# 2023-04-10.net
KiCad netlist of a schematic drawn in Altium Designer
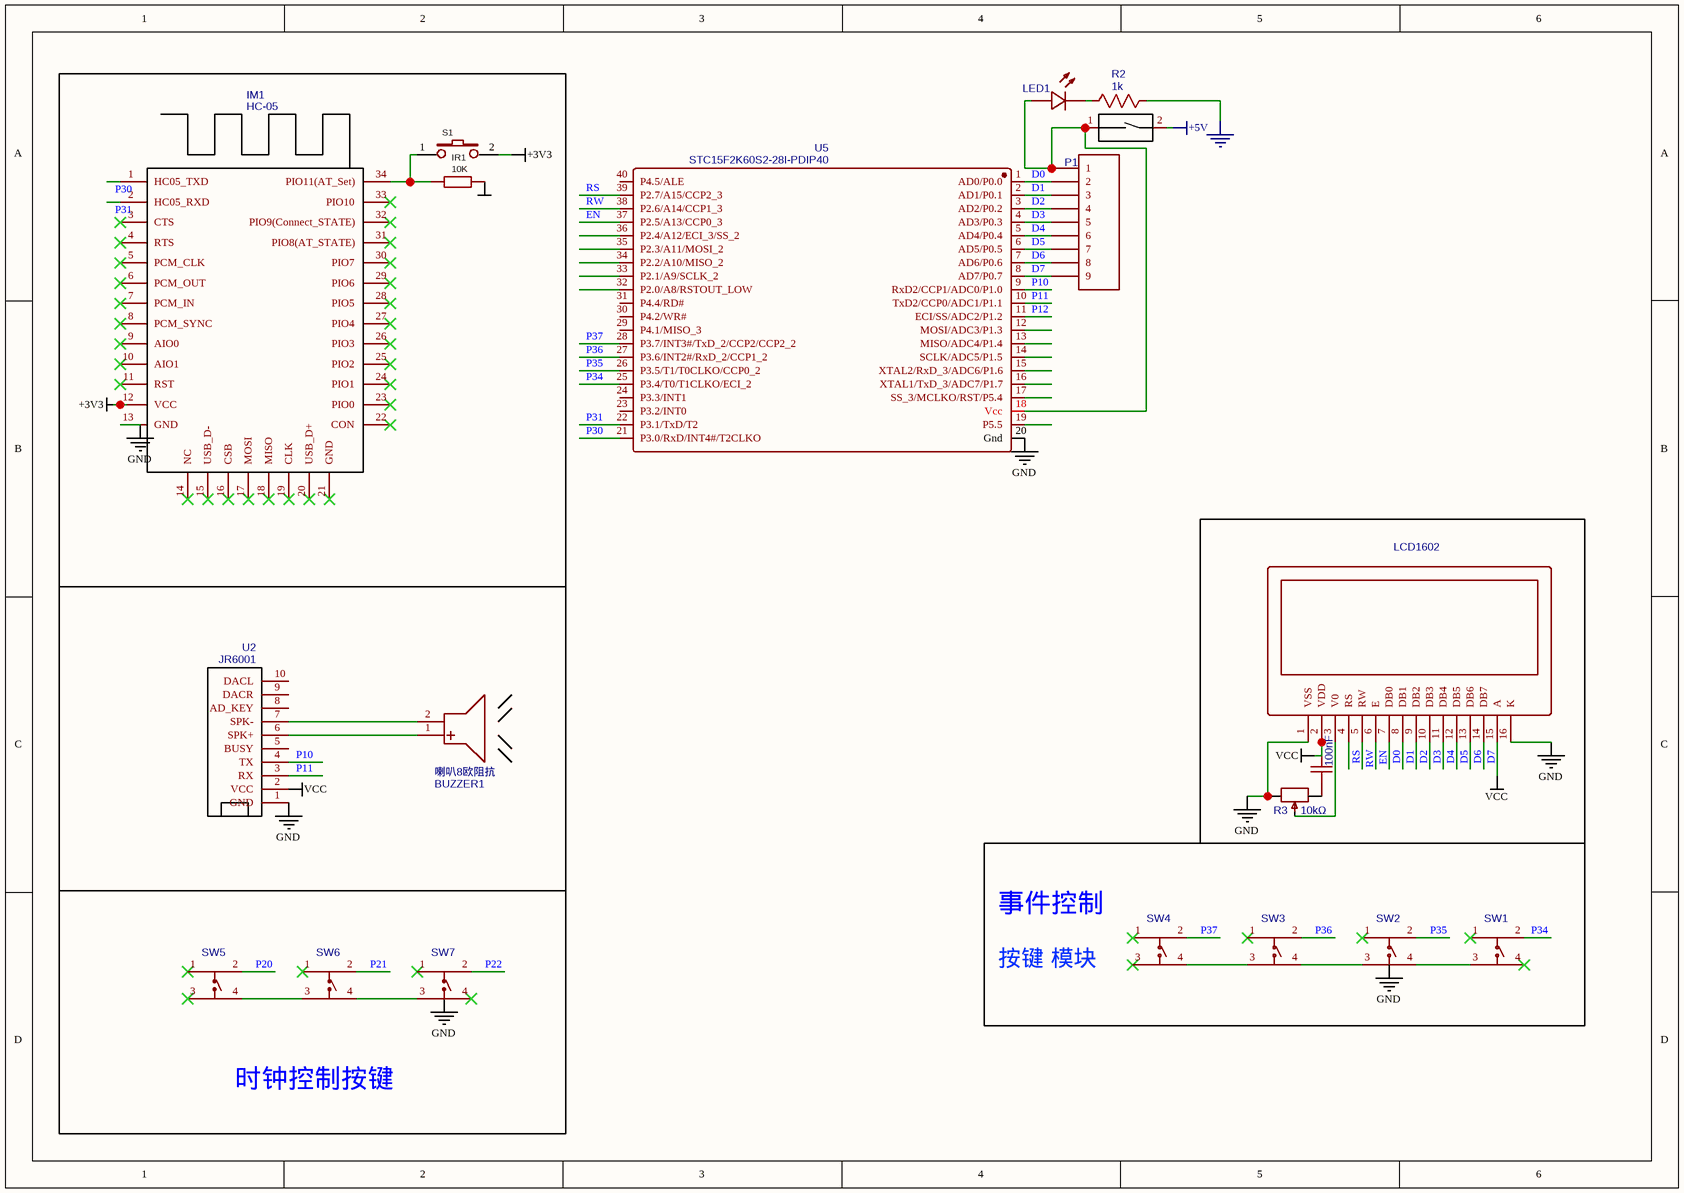
[diagram p0: 多功能遥控门铃的设计_2023-04-10.schdoc]

(export (version "E")
  (design (tool "Eeschema 10.0.6"))
  (components
    (comp (ref "BUZZER1")
      (value "喇叭8欧阻抗")
      (fields
        (field (name "BOM_SUPPLIER PART") "C265130")
        (field (name "BOM_MANUFACTURER PART") "GMD0955YB-12V2700")
        (field (name "CONTRIBUTOR") "kennen")
      )
      (libsource (lib "altium-import") (part "root_0_喇叭8欧阻抗_"))
    )
    (comp (ref "C1")
      (value "100nF")
      (fields
        (field (name "BOM_SUPPLIER PART") "C327271")
        (field (name "BOM_MANUFACTURER PART") "CC0402MRY5V8BB104")
        (field (name "CONTRIBUTOR") "LCSC")
      )
      (libsource (lib "altium-import") (part "root_1_100nF_"))
    )
    (comp (ref "DIP1")
      (value "VDG/S-01L blue")
      (fields (field (name "BOM_SUPPLIER PART") "C47086"))
      (libsource (lib "altium-import") (part "root_0_VDG/S-01L blue_"))
    )
    (comp (ref "IKEY1")
      (value "S1")
      (fields
        (field (name "BOM_MANUFACTURER PART") "直插轻触开关 6*6*9.5")
        (field (name "CONTRIBUTOR") "Zhang9999999")
      )
      (libsource (lib "altium-import") (part "root_0_S1_"))
    )
    (comp (ref "IM1")
      (value "HC-05")
      (fields (field (name "CONTRIBUTOR") "luohaiyang"))
      (libsource (lib "altium-import") (part "root_0_HC-05_"))
    )
    (comp (ref "IR1")
      (value "10K")
      (fields (field (name "BOM_MANUFACTURER PART") "?"))
      (libsource (lib "altium-import") (part "root_0_10K_"))
    )
    (comp (ref "LCD1602")
      (value "1")
      (fields
        (field (name "BOM_MANUFACTURER PART") "LCM1602K-NSW-BBW-33V33")
        (field (name "BOM_SUPPLIER PART") "C83272")
      )
      (libsource (lib "altium-import") (part "root_0_1_"))
    )
    (comp (ref "LED1")
      (value "LED-3MM")
      (fields
        (field (name "BOM_SUPPLIER PART") "C99772")
        (field (name "BOM_MANUFACTURER PART") "204-10SURD/S530-A3")
      )
      (libsource (lib "altium-import") (part "root_0_LED-3MM_"))
    )
    (comp (ref "P1")
      (value "SIP9")
      (fields (field (name "BOM_MANUFACTURER PART") "?"))
      (libsource (lib "altium-import") (part "root_0_SIP9_"))
    )
    (comp (ref "R2")
      (value "1k")
      (fields (field (name "BOM_MANUFACTURER PART") "?"))
      (libsource (lib "altium-import") (part "root_2_1k_"))
    )
    (comp (ref "R3")
      (value "10kΩ")
      (fields
        (field (name "BOM_MANUFACTURER PART") "3296W-1-103LF")
        (field (name "BOM_SUPPLIER PART") "C34846")
      )
      (libsource (lib "altium-import") (part "root_1_10kΩ_"))
    )
    (comp (ref "SW1")
      (value "KH-6X6X6H-STM")
      (fields (field (name "BOM_SUPPLIER PART") "C2837532") (field (name "CONTRIBUTOR") "LCSC"))
      (libsource (lib "altium-import") (part "root_0_KH-6X6X6H-STM_"))
    )
    (comp (ref "SW2")
      (value "KH-6X6X6H-STM")
      (fields (field (name "BOM_SUPPLIER PART") "C2837532") (field (name "CONTRIBUTOR") "LCSC"))
      (libsource (lib "altium-import") (part "root_0_KH-6X6X6H-STM_"))
    )
    (comp (ref "SW3")
      (value "KH-6X6X6H-STM")
      (fields (field (name "BOM_SUPPLIER PART") "C2837532") (field (name "CONTRIBUTOR") "LCSC"))
      (libsource (lib "altium-import") (part "root_0_KH-6X6X6H-STM_"))
    )
    (comp (ref "SW4")
      (value "KH-6X6X6H-STM")
      (fields (field (name "BOM_SUPPLIER PART") "C2837532") (field (name "CONTRIBUTOR") "LCSC"))
      (libsource (lib "altium-import") (part "root_0_KH-6X6X6H-STM_"))
    )
    (comp (ref "SW5")
      (value "KH-6X6X6H-STM")
      (fields (field (name "BOM_SUPPLIER PART") "C2837532") (field (name "CONTRIBUTOR") "LCSC"))
      (libsource (lib "altium-import") (part "root_0_KH-6X6X6H-STM_"))
    )
    (comp (ref "SW6")
      (value "KH-6X6X6H-STM")
      (fields (field (name "BOM_SUPPLIER PART") "C2837532") (field (name "CONTRIBUTOR") "LCSC"))
      (libsource (lib "altium-import") (part "root_0_KH-6X6X6H-STM_"))
    )
    (comp (ref "SW7")
      (value "KH-6X6X6H-STM")
      (fields (field (name "BOM_SUPPLIER PART") "C2837532") (field (name "CONTRIBUTOR") "LCSC"))
      (libsource (lib "altium-import") (part "root_0_KH-6X6X6H-STM_"))
    )
    (comp (ref "U2")
      (value "JR6001")
      (fields (field (name "CONTRIBUTOR") "212308jiangyuhao"))
      (libsource (lib "altium-import") (part "root_0_JR6001_"))
    )
    (comp (ref "U5")
      (value "STC15F2K60S2-28I-PDIP40")
      (fields (field (name "BOM_SUPPLIER PART") "C57308"))
      (libsource (lib "altium-import") (part "root_0_STC15F2K60S2-28I-PDIP40_"))
    )
  )
  (nets
    (net (code "1") (name "+3V3") (class "Default")
      (node (ref "IKEY1") (pin "2") (pinfunction "3_2") (pintype "passive"))
      (node (ref "IM1") (pin "12") (pinfunction "VCC_12") (pintype "passive"))
    )
    (net (code "2") (name "+5V") (class "Default")
      (node (ref "DIP1") (pin "2") (pinfunction "2_2") (pintype "passive"))
    )
    (net (code "3") (name "/D0") (class "Default")
      (node (ref "LCD1602") (pin "7") (pinfunction "DB0_7") (pintype "passive"))
      (node (ref "P1") (pin "2") (pinfunction "2_2") (pintype "passive"))
      (node (ref "U5") (pin "1") (pinfunction "AD0/P0.0_1") (pintype "passive"))
    )
    (net (code "4") (name "/D1") (class "Default")
      (node (ref "LCD1602") (pin "8") (pinfunction "DB1_8") (pintype "passive"))
      (node (ref "P1") (pin "3") (pinfunction "3_3") (pintype "passive"))
      (node (ref "U5") (pin "2") (pinfunction "AD1/P0.1_2") (pintype "passive"))
    )
    (net (code "5") (name "/D2") (class "Default")
      (node (ref "LCD1602") (pin "9") (pinfunction "DB2_9") (pintype "passive"))
      (node (ref "P1") (pin "4") (pinfunction "4_4") (pintype "passive"))
      (node (ref "U5") (pin "3") (pinfunction "AD2/P0.2_3") (pintype "passive"))
    )
    (net (code "6") (name "/D3") (class "Default")
      (node (ref "LCD1602") (pin "10") (pinfunction "DB3_10") (pintype "passive"))
      (node (ref "P1") (pin "5") (pinfunction "5_5") (pintype "passive"))
      (node (ref "U5") (pin "4") (pinfunction "AD3/P0.3_4") (pintype "passive"))
    )
    (net (code "7") (name "/D4") (class "Default")
      (node (ref "LCD1602") (pin "11") (pinfunction "DB4_11") (pintype "passive"))
      (node (ref "P1") (pin "6") (pinfunction "6_6") (pintype "passive"))
      (node (ref "U5") (pin "5") (pinfunction "AD4/P0.4_5") (pintype "passive"))
    )
    (net (code "8") (name "/D5") (class "Default")
      (node (ref "LCD1602") (pin "12") (pinfunction "DB5_12") (pintype "passive"))
      (node (ref "P1") (pin "7") (pinfunction "7_7") (pintype "passive"))
      (node (ref "U5") (pin "6") (pinfunction "AD5/P0.5_6") (pintype "passive"))
    )
    (net (code "9") (name "/D6") (class "Default")
      (node (ref "LCD1602") (pin "13") (pinfunction "DB6_13") (pintype "passive"))
      (node (ref "P1") (pin "8") (pinfunction "8_8") (pintype "passive"))
      (node (ref "U5") (pin "7") (pinfunction "AD6/P0.6_7") (pintype "passive"))
    )
    (net (code "10") (name "/D7") (class "Default")
      (node (ref "LCD1602") (pin "14") (pinfunction "DB7_14") (pintype "passive"))
      (node (ref "P1") (pin "9") (pinfunction "9_9") (pintype "passive"))
      (node (ref "U5") (pin "8") (pinfunction "AD7/P0.7_8") (pintype "passive"))
    )
    (net (code "11") (name "/EN") (class "Default")
      (node (ref "LCD1602") (pin "6") (pinfunction "E_6") (pintype "passive"))
      (node (ref "U5") (pin "37") (pinfunction "P2.5/A13/CCP0_3_37") (pintype "passive"))
    )
    (net (code "12") (name "/P10") (class "Default")
      (node (ref "U2") (pin "4") (pinfunction "TX_4") (pintype "passive"))
      (node (ref "U5") (pin "9") (pinfunction "RxD2/CCP1/ADC0/P1.0_9") (pintype "passive"))
    )
    (net (code "13") (name "/P11") (class "Default")
      (node (ref "U2") (pin "3") (pinfunction "RX_3") (pintype "passive"))
      (node (ref "U5") (pin "10") (pinfunction "TxD2/CCP0/ADC1/P1.1_10") (pintype "passive"))
    )
    (net (code "14") (name "/P12") (class "Default")
      (node (ref "U5") (pin "11") (pinfunction "ECI/SS/ADC2/P1.2_11") (pintype "passive"))
    )
    (net (code "15") (name "/P20") (class "Default")
      (node (ref "SW5") (pin "2") (pinfunction "B_2") (pintype "passive"))
    )
    (net (code "16") (name "/P21") (class "Default")
      (node (ref "SW6") (pin "2") (pinfunction "B_2") (pintype "passive"))
    )
    (net (code "17") (name "/P22") (class "Default")
      (node (ref "SW7") (pin "2") (pinfunction "B_2") (pintype "passive"))
    )
    (net (code "18") (name "/P30") (class "Default")
      (node (ref "U5") (pin "21") (pinfunction "P3.0/RxD/INT4#/T2CLKO_21") (pintype "passive"))
    )
    (net (code "19") (name "/P31") (class "Default")
      (node (ref "U5") (pin "22") (pinfunction "P3.1/TxD/T2_22") (pintype "passive"))
    )
    (net (code "20") (name "/P34") (class "Default")
      (node (ref "SW1") (pin "2") (pinfunction "B_2") (pintype "passive"))
      (node (ref "U5") (pin "25") (pinfunction "P3.4/T0/T1CLKO/ECI_2_25") (pintype "passive"))
    )
    (net (code "21") (name "/P35") (class "Default")
      (node (ref "SW2") (pin "2") (pinfunction "B_2") (pintype "passive"))
      (node (ref "U5") (pin "26") (pinfunction "P3.5/T1/T0CLKO/CCP0_2_26") (pintype "passive"))
    )
    (net (code "22") (name "/P36") (class "Default")
      (node (ref "SW3") (pin "2") (pinfunction "B_2") (pintype "passive"))
      (node (ref "U5") (pin "27") (pinfunction "P3.6/INT2#/RxD_2/CCP1_2_27") (pintype "passive"))
    )
    (net (code "23") (name "/P37") (class "Default")
      (node (ref "SW4") (pin "2") (pinfunction "B_2") (pintype "passive"))
      (node (ref "U5") (pin "28") (pinfunction "P3.7/INT3#/TxD_2/CCP2/CCP2_2_28") (pintype "passive"))
    )
    (net (code "24") (name "/RS") (class "Default")
      (node (ref "LCD1602") (pin "4") (pinfunction "RS_4") (pintype "passive"))
      (node (ref "U5") (pin "39") (pinfunction "P2.7/A15/CCP2_3_39") (pintype "passive"))
    )
    (net (code "25") (name "/RW") (class "Default")
      (node (ref "LCD1602") (pin "5") (pinfunction "RW_5") (pintype "passive"))
      (node (ref "U5") (pin "38") (pinfunction "P2.6/A14/CCP1_3_38") (pintype "passive"))
    )
    (net (code "26") (name "GND") (class "Default")
      (node (ref "IM1") (pin "13") (pinfunction "GND_13") (pintype "passive"))
      (node (ref "IR1") (pin "2") (pinfunction "2_2") (pintype "passive"))
      (node (ref "LCD1602") (pin "1") (pinfunction "VSS_1") (pintype "passive"))
      (node (ref "LCD1602") (pin "16") (pinfunction "K_16") (pintype "passive"))
      (node (ref "R2") (pin "1") (pinfunction "1_1") (pintype "passive"))
      (node (ref "R3") (pin "1") (pinfunction "1_1") (pintype "passive"))
      (node (ref "U2") (pin "1") (pinfunction "GND_1") (pintype "passive"))
      (node (ref "U5") (pin "20") (pinfunction "Gnd_20") (pintype "passive"))
    )
    (net (code "27") (name "Net-(BUZZER1-+)") (class "Default")
      (node (ref "BUZZER1") (pin "1") (pinfunction "+_1") (pintype "passive"))
      (node (ref "U2") (pin "6") (pinfunction "SPK+_6") (pintype "passive"))
    )
    (net (code "28") (name "Net-(BUZZER1--)") (class "Default")
      (node (ref "BUZZER1") (pin "2") (pinfunction "-_2") (pintype "passive"))
      (node (ref "U2") (pin "7") (pinfunction "SPK-_7") (pintype "passive"))
    )
    (net (code "29") (name "Net-(C1-Pad1)") (class "Default")
      (node (ref "C1") (pin "1") (pinfunction "1_1") (pintype "passive"))
      (node (ref "R3") (pin "3") (pinfunction "3_3") (pintype "passive"))
    )
    (net (code "30") (name "Net-(IM1-PIO11(AT_Set))") (class "Default")
      (node (ref "IKEY1") (pin "1") (pinfunction "1_1") (pintype "passive"))
      (node (ref "IM1") (pin "34") (pinfunction "PIO11(AT_Set)_34") (pintype "passive"))
      (node (ref "IR1") (pin "1") (pinfunction "1_1") (pintype "passive"))
    )
    (net (code "31") (name "Net-(LCD1602-V0)") (class "Default")
      (node (ref "LCD1602") (pin "3") (pinfunction "V0_3") (pintype "passive"))
      (node (ref "R3") (pin "2") (pinfunction "2_2") (pintype "passive"))
    )
    (net (code "32") (name "Net-(LED1-+)") (class "Default")
      (node (ref "DIP1") (pin "1") (pinfunction "1_1") (pintype "passive"))
      (node (ref "LED1") (pin "1") (pinfunction "+_1") (pintype "passive"))
      (node (ref "P1") (pin "1") (pinfunction "1_1") (pintype "passive"))
      (node (ref "U5") (pin "18") (pinfunction "Vcc_18") (pintype "passive"))
    )
    (net (code "33") (name "Net-(LED1--)") (class "Default")
      (node (ref "LED1") (pin "2") (pinfunction "-_2") (pintype "passive"))
      (node (ref "R2") (pin "2") (pinfunction "2_2") (pintype "passive"))
    )
    (net (code "34") (name "Net-(SW1-C)") (class "Default")
      (node (ref "SW1") (pin "3") (pinfunction "C_3") (pintype "passive"))
      (node (ref "SW2") (pin "4") (pinfunction "D_4") (pintype "passive"))
    )
    (net (code "35") (name "Net-(SW2-C)") (class "Default")
      (node (ref "SW2") (pin "3") (pinfunction "C_3") (pintype "passive"))
      (node (ref "SW3") (pin "4") (pinfunction "D_4") (pintype "passive"))
    )
    (net (code "36") (name "Net-(SW3-C)") (class "Default")
      (node (ref "SW3") (pin "3") (pinfunction "C_3") (pintype "passive"))
      (node (ref "SW4") (pin "4") (pinfunction "D_4") (pintype "passive"))
    )
    (net (code "37") (name "Net-(SW5-D)") (class "Default")
      (node (ref "SW5") (pin "4") (pinfunction "D_4") (pintype "passive"))
      (node (ref "SW6") (pin "3") (pinfunction "C_3") (pintype "passive"))
    )
    (net (code "38") (name "Net-(SW6-D)") (class "Default")
      (node (ref "SW6") (pin "4") (pinfunction "D_4") (pintype "passive"))
      (node (ref "SW7") (pin "3") (pinfunction "C_3") (pintype "passive"))
    )
    (net (code "39") (name "VCC") (class "Default")
      (node (ref "C1") (pin "2") (pinfunction "2_2") (pintype "passive"))
      (node (ref "LCD1602") (pin "15") (pinfunction "A_15") (pintype "passive"))
      (node (ref "LCD1602") (pin "2") (pinfunction "VDD_2") (pintype "passive"))
      (node (ref "U2") (pin "2") (pinfunction "VCC_2") (pintype "passive"))
    )
    (net (code "40") (name "unconnected-(IM1-AIO0-Pad9)") (class "Default")
      (node (ref "IM1") (pin "9") (pinfunction "AIO0_9") (pintype "passive+no_connect"))
    )
    (net (code "41") (name "unconnected-(IM1-AIO1-Pad10)") (class "Default")
      (node (ref "IM1") (pin "10") (pinfunction "AIO1_10") (pintype "passive+no_connect"))
    )
    (net (code "42") (name "unconnected-(IM1-CLK-Pad19)") (class "Default")
      (node (ref "IM1") (pin "19") (pinfunction "CLK_19") (pintype "passive+no_connect"))
    )
    (net (code "43") (name "unconnected-(IM1-CON-Pad22)") (class "Default")
      (node (ref "IM1") (pin "22") (pinfunction "CON_22") (pintype "passive+no_connect"))
    )
    (net (code "44") (name "unconnected-(IM1-CSB-Pad16)") (class "Default")
      (node (ref "IM1") (pin "16") (pinfunction "CSB_16") (pintype "passive+no_connect"))
    )
    (net (code "45") (name "unconnected-(IM1-CTS-Pad3)") (class "Default")
      (node (ref "IM1") (pin "3") (pinfunction "CTS_3") (pintype "passive+no_connect"))
    )
    (net (code "46") (name "unconnected-(IM1-GND-Pad21)") (class "Default")
      (node (ref "IM1") (pin "21") (pinfunction "GND_21") (pintype "passive+no_connect"))
    )
    (net (code "47") (name "unconnected-(IM1-HC05_RXD-Pad2)") (class "Default")
      (node (ref "IM1") (pin "2") (pinfunction "HC05_RXD_2") (pintype "passive"))
    )
    (net (code "48") (name "unconnected-(IM1-HC05_TXD-Pad1)") (class "Default")
      (node (ref "IM1") (pin "1") (pinfunction "HC05_TXD_1") (pintype "passive"))
    )
    (net (code "49") (name "unconnected-(IM1-MISO-Pad18)") (class "Default")
      (node (ref "IM1") (pin "18") (pinfunction "MISO_18") (pintype "passive+no_connect"))
    )
    (net (code "50") (name "unconnected-(IM1-MOSI-Pad17)") (class "Default")
      (node (ref "IM1") (pin "17") (pinfunction "MOSI_17") (pintype "passive+no_connect"))
    )
    (net (code "51") (name "unconnected-(IM1-NC-Pad14)") (class "Default")
      (node (ref "IM1") (pin "14") (pinfunction "NC_14") (pintype "passive+no_connect"))
    )
    (net (code "52") (name "unconnected-(IM1-PCM_CLK-Pad5)") (class "Default")
      (node (ref "IM1") (pin "5") (pinfunction "PCM_CLK_5") (pintype "passive+no_connect"))
    )
    (net (code "53") (name "unconnected-(IM1-PCM_IN-Pad7)") (class "Default")
      (node (ref "IM1") (pin "7") (pinfunction "PCM_IN_7") (pintype "passive+no_connect"))
    )
    (net (code "54") (name "unconnected-(IM1-PCM_OUT-Pad6)") (class "Default")
      (node (ref "IM1") (pin "6") (pinfunction "PCM_OUT_6") (pintype "passive+no_connect"))
    )
    (net (code "55") (name "unconnected-(IM1-PCM_SYNC-Pad8)") (class "Default")
      (node (ref "IM1") (pin "8") (pinfunction "PCM_SYNC_8") (pintype "passive+no_connect"))
    )
    (net (code "56") (name "unconnected-(IM1-PIO0-Pad23)") (class "Default")
      (node (ref "IM1") (pin "23") (pinfunction "PIO0_23") (pintype "passive+no_connect"))
    )
    (net (code "57") (name "unconnected-(IM1-PIO1-Pad24)") (class "Default")
      (node (ref "IM1") (pin "24") (pinfunction "PIO1_24") (pintype "passive+no_connect"))
    )
    (net (code "58") (name "unconnected-(IM1-PIO2-Pad25)") (class "Default")
      (node (ref "IM1") (pin "25") (pinfunction "PIO2_25") (pintype "passive+no_connect"))
    )
    (net (code "59") (name "unconnected-(IM1-PIO3-Pad26)") (class "Default")
      (node (ref "IM1") (pin "26") (pinfunction "PIO3_26") (pintype "passive+no_connect"))
    )
    (net (code "60") (name "unconnected-(IM1-PIO4-Pad27)") (class "Default")
      (node (ref "IM1") (pin "27") (pinfunction "PIO4_27") (pintype "passive+no_connect"))
    )
    (net (code "61") (name "unconnected-(IM1-PIO5-Pad28)") (class "Default")
      (node (ref "IM1") (pin "28") (pinfunction "PIO5_28") (pintype "passive+no_connect"))
    )
    (net (code "62") (name "unconnected-(IM1-PIO6-Pad29)") (class "Default")
      (node (ref "IM1") (pin "29") (pinfunction "PIO6_29") (pintype "passive+no_connect"))
    )
    (net (code "63") (name "unconnected-(IM1-PIO7-Pad30)") (class "Default")
      (node (ref "IM1") (pin "30") (pinfunction "PIO7_30") (pintype "passive+no_connect"))
    )
    (net (code "64") (name "unconnected-(IM1-PIO8(AT_STATE)-Pad31)") (class "Default")
      (node (ref "IM1") (pin "31") (pinfunction "PIO8(AT_STATE)_31") (pintype "passive+no_connect"))
    )
    (net (code "65") (name "unconnected-(IM1-PIO9(Connect_STATE)-Pad32)") (class "Default")
      (node (ref "IM1") (pin "32") (pinfunction "PIO9(Connect_STATE)_32") (pintype "passive+no_connect"))
    )
    (net (code "66") (name "unconnected-(IM1-PIO10-Pad33)") (class "Default")
      (node (ref "IM1") (pin "33") (pinfunction "PIO10_33") (pintype "passive+no_connect"))
    )
    (net (code "67") (name "unconnected-(IM1-RST-Pad11)") (class "Default")
      (node (ref "IM1") (pin "11") (pinfunction "RST_11") (pintype "passive+no_connect"))
    )
    (net (code "68") (name "unconnected-(IM1-RTS-Pad4)") (class "Default")
      (node (ref "IM1") (pin "4") (pinfunction "RTS_4") (pintype "passive+no_connect"))
    )
    (net (code "69") (name "unconnected-(IM1-USB_D+-Pad20)") (class "Default")
      (node (ref "IM1") (pin "20") (pinfunction "USB_D+_20") (pintype "passive+no_connect"))
    )
    (net (code "70") (name "unconnected-(IM1-USB_D--Pad15)") (class "Default")
      (node (ref "IM1") (pin "15") (pinfunction "USB_D-_15") (pintype "passive+no_connect"))
    )
    (net (code "71") (name "unconnected-(SW1-A-Pad1)") (class "Default")
      (node (ref "SW1") (pin "1") (pinfunction "A_1") (pintype "passive+no_connect"))
    )
    (net (code "72") (name "unconnected-(SW1-D-Pad4)") (class "Default")
      (node (ref "SW1") (pin "4") (pinfunction "D_4") (pintype "passive+no_connect"))
    )
    (net (code "73") (name "unconnected-(SW2-A-Pad1)") (class "Default")
      (node (ref "SW2") (pin "1") (pinfunction "A_1") (pintype "passive+no_connect"))
    )
    (net (code "74") (name "unconnected-(SW3-A-Pad1)") (class "Default")
      (node (ref "SW3") (pin "1") (pinfunction "A_1") (pintype "passive+no_connect"))
    )
    (net (code "75") (name "unconnected-(SW4-A-Pad1)") (class "Default")
      (node (ref "SW4") (pin "1") (pinfunction "A_1") (pintype "passive+no_connect"))
    )
    (net (code "76") (name "unconnected-(SW4-C-Pad3)") (class "Default")
      (node (ref "SW4") (pin "3") (pinfunction "C_3") (pintype "passive+no_connect"))
    )
    (net (code "77") (name "unconnected-(SW5-A-Pad1)") (class "Default")
      (node (ref "SW5") (pin "1") (pinfunction "A_1") (pintype "passive+no_connect"))
    )
    (net (code "78") (name "unconnected-(SW5-C-Pad3)") (class "Default")
      (node (ref "SW5") (pin "3") (pinfunction "C_3") (pintype "passive+no_connect"))
    )
    (net (code "79") (name "unconnected-(SW6-A-Pad1)") (class "Default")
      (node (ref "SW6") (pin "1") (pinfunction "A_1") (pintype "passive+no_connect"))
    )
    (net (code "80") (name "unconnected-(SW7-A-Pad1)") (class "Default")
      (node (ref "SW7") (pin "1") (pinfunction "A_1") (pintype "passive+no_connect"))
    )
    (net (code "81") (name "unconnected-(SW7-D-Pad4)") (class "Default")
      (node (ref "SW7") (pin "4") (pinfunction "D_4") (pintype "passive+no_connect"))
    )
    (net (code "82") (name "unconnected-(U2-AD_KEY-Pad8)") (class "Default")
      (node (ref "U2") (pin "8") (pinfunction "AD_KEY_8") (pintype "passive"))
    )
    (net (code "83") (name "unconnected-(U2-BUSY-Pad5)") (class "Default")
      (node (ref "U2") (pin "5") (pinfunction "BUSY_5") (pintype "passive"))
    )
    (net (code "84") (name "unconnected-(U2-DACL-Pad10)") (class "Default")
      (node (ref "U2") (pin "10") (pinfunction "DACL_10") (pintype "passive"))
    )
    (net (code "85") (name "unconnected-(U2-DACR-Pad9)") (class "Default")
      (node (ref "U2") (pin "9") (pinfunction "DACR_9") (pintype "passive"))
    )
    (net (code "86") (name "unconnected-(U5-MISO{slash}ADC4{slash}P1.4-Pad13)") (class "Default")
      (node (ref "U5") (pin "13") (pinfunction "MISO/ADC4/P1.4_13") (pintype "passive"))
    )
    (net (code "87") (name "unconnected-(U5-MOSI{slash}ADC3{slash}P1.3-Pad12)") (class "Default")
      (node (ref "U5") (pin "12") (pinfunction "MOSI/ADC3/P1.3_12") (pintype "passive"))
    )
    (net (code "88") (name "unconnected-(U5-P2.0{slash}A8{slash}RSTOUT_LOW-Pad32)") (class "Default")
      (node (ref "U5") (pin "32") (pinfunction "P2.0/A8/RSTOUT_LOW_32") (pintype "passive"))
    )
    (net (code "89") (name "unconnected-(U5-P2.1{slash}A9{slash}SCLK_2-Pad33)") (class "Default")
      (node (ref "U5") (pin "33") (pinfunction "P2.1/A9/SCLK_2_33") (pintype "passive"))
    )
    (net (code "90") (name "unconnected-(U5-P2.2{slash}A10{slash}MISO_2-Pad34)") (class "Default")
      (node (ref "U5") (pin "34") (pinfunction "P2.2/A10/MISO_2_34") (pintype "passive"))
    )
    (net (code "91") (name "unconnected-(U5-P2.3{slash}A11{slash}MOSI_2-Pad35)") (class "Default")
      (node (ref "U5") (pin "35") (pinfunction "P2.3/A11/MOSI_2_35") (pintype "passive"))
    )
    (net (code "92") (name "unconnected-(U5-P2.4{slash}A12{slash}ECI_3{slash}SS_2-Pad36)") (class "Default")
      (node (ref "U5") (pin "36") (pinfunction "P2.4/A12/ECI_3/SS_2_36") (pintype "passive"))
    )
    (net (code "93") (name "unconnected-(U5-P3.2{slash}INT0-Pad23)") (class "Default")
      (node (ref "U5") (pin "23") (pinfunction "P3.2/INT0_23") (pintype "passive"))
    )
    (net (code "94") (name "unconnected-(U5-P3.3{slash}INT1-Pad24)") (class "Default")
      (node (ref "U5") (pin "24") (pinfunction "P3.3/INT1_24") (pintype "passive"))
    )
    (net (code "95") (name "unconnected-(U5-P4.1{slash}MISO_3-Pad29)") (class "Default")
      (node (ref "U5") (pin "29") (pinfunction "P4.1/MISO_3_29") (pintype "passive"))
    )
    (net (code "96") (name "unconnected-(U5-P4.2{slash}WR#-Pad30)") (class "Default")
      (node (ref "U5") (pin "30") (pinfunction "P4.2/WR#_30") (pintype "passive"))
    )
    (net (code "97") (name "unconnected-(U5-P4.4{slash}RD#-Pad31)") (class "Default")
      (node (ref "U5") (pin "31") (pinfunction "P4.4/RD#_31") (pintype "passive"))
    )
    (net (code "98") (name "unconnected-(U5-P4.5{slash}ALE-Pad40)") (class "Default")
      (node (ref "U5") (pin "40") (pinfunction "P4.5/ALE_40") (pintype "passive"))
    )
    (net (code "99") (name "unconnected-(U5-P5.5-Pad19)") (class "Default")
      (node (ref "U5") (pin "19") (pinfunction "P5.5_19") (pintype "passive"))
    )
    (net (code "100") (name "unconnected-(U5-SCLK{slash}ADC5{slash}P1.5-Pad14)") (class "Default")
      (node (ref "U5") (pin "14") (pinfunction "SCLK/ADC5/P1.5_14") (pintype "passive"))
    )
    (net (code "101") (name "unconnected-(U5-SS_3{slash}MCLKO{slash}RST{slash}P5.4-Pad17)") (class "Default")
      (node (ref "U5") (pin "17") (pinfunction "SS_3/MCLKO/RST/P5.4_17") (pintype "passive"))
    )
    (net (code "102") (name "unconnected-(U5-XTAL1{slash}TxD_3{slash}ADC7{slash}P1.7-Pad16)") (class "Default")
      (node (ref "U5") (pin "16") (pinfunction "XTAL1/TxD_3/ADC7/P1.7_16") (pintype "passive"))
    )
    (net (code "103") (name "unconnected-(U5-XTAL2{slash}RxD_3{slash}ADC6{slash}P1.6-Pad15)") (class "Default")
      (node (ref "U5") (pin "15") (pinfunction "XTAL2/RxD_3/ADC6/P1.6_15") (pintype "passive"))
    )
  )
)
